# TopLevelMCU.net
KiCad netlist of a schematic drawn in Altium Designer
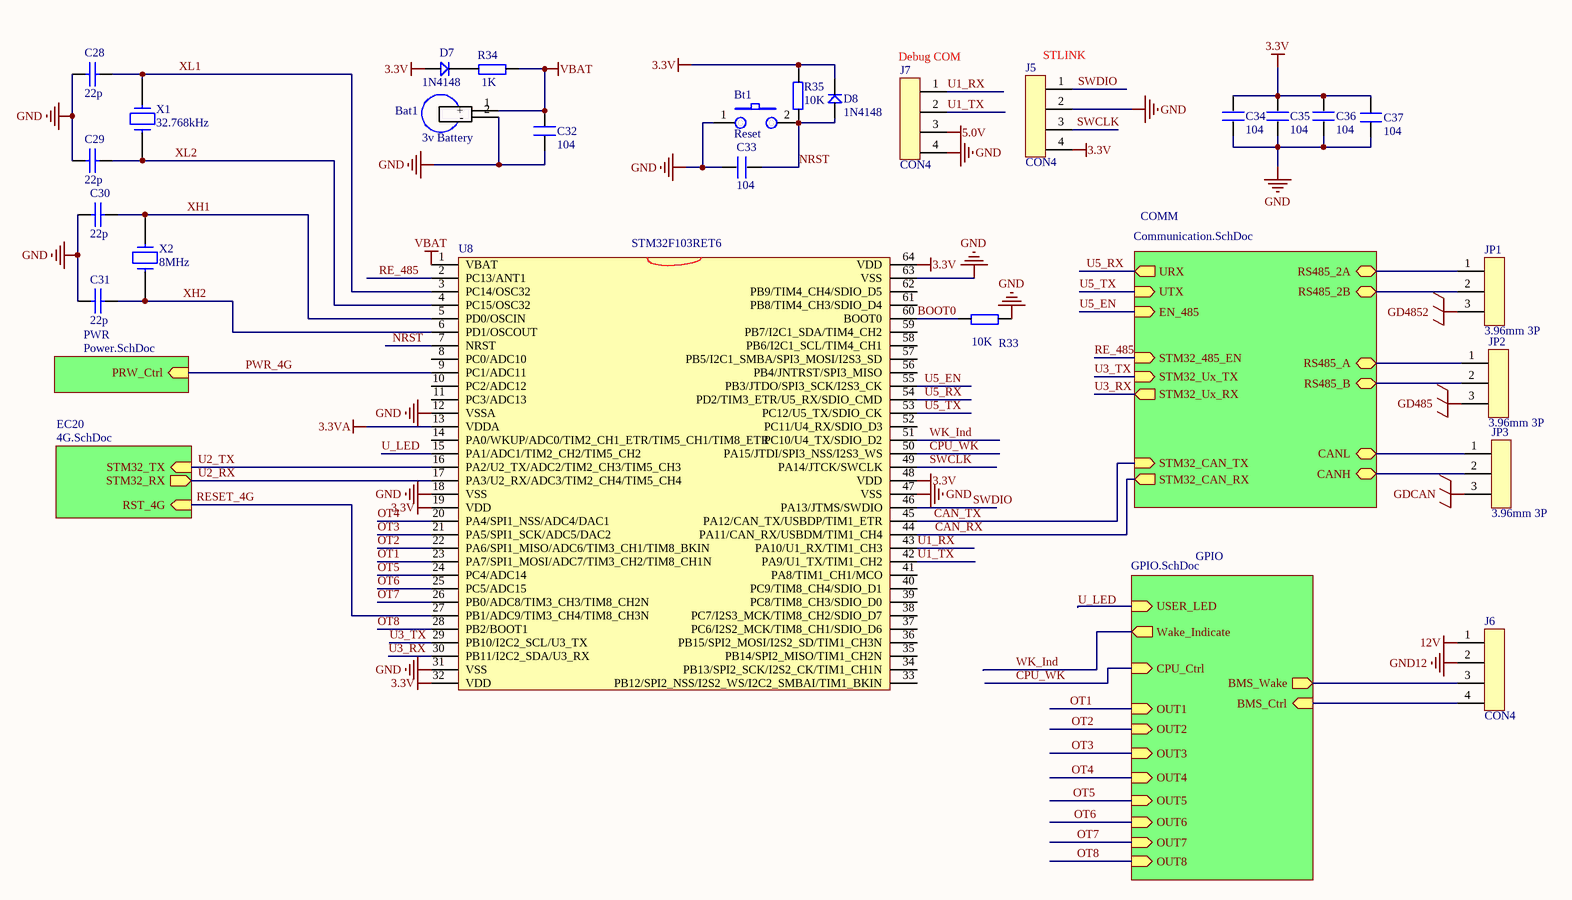
[diagram p0: TopLevelMCU.SchDoc]

(export (version "E")
  (design (tool "Eeschema 10.0.6"))
  (components
    (comp (ref "Bat1") (value "3v Battery") (footprint "BATM") (libsource (lib "stm32") (part "MS621FE")))
    (comp (ref "Bt1")
      (value "Reset")
      (footprint "mypcb:3*6*2.5贴片 微动开关")
      (libsource (lib "stm32") (part "PUSH BUTTON"))
    )
    (comp (ref "C28")
      (value "22p")
      (footprint "0603_C")
      (description "Capacitor")
      (libsource (lib "PLC1") (part "CAP"))
    )
    (comp (ref "C29")
      (value "22p")
      (footprint "0603_C")
      (description "Capacitor")
      (libsource (lib "PLC1") (part "CAP"))
    )
    (comp (ref "C30")
      (value "22p")
      (footprint "0603_C")
      (description "Capacitor")
      (libsource (lib "PLC1") (part "CAP"))
    )
    (comp (ref "C31")
      (value "22p")
      (footprint "0603_C")
      (description "Capacitor")
      (libsource (lib "PLC1") (part "CAP"))
    )
    (comp (ref "C32") (value "104") (footprint "0603_C") (libsource (lib "CORE") (part "C")))
    (comp (ref "C33") (value "104") (footprint "0603_C") (libsource (lib "CORE") (part "C")))
    (comp (ref "C34") (value "104") (footprint "0603_C") (libsource (lib "CORE") (part "C")))
    (comp (ref "C35") (value "104") (footprint "0603_C") (libsource (lib "CORE") (part "C")))
    (comp (ref "C36") (value "104") (footprint "0603_C") (libsource (lib "CORE") (part "C")))
    (comp (ref "C37") (value "104") (footprint "0603_C") (libsource (lib "CORE") (part "C")))
    (comp (ref "D7") (value "1N4148") (footprint "SOD-323") (libsource (lib "CORE") (part "D")))
    (comp (ref "D8") (value "1N4148") (footprint "SOD-323") (libsource (lib "CORE") (part "D")))
    (comp (ref "J5") (value "CON4") (footprint "CON4(2.54)") (libsource (lib "mysch") (part "CON4")))
    (comp (ref "J6") (value "CON4") (footprint "CON4(2.54)") (libsource (lib "BatteryIot-V3") (part "CON4")))
    (comp (ref "J7") (value "CON4") (footprint "CON4(2.54)") (libsource (lib "mysch") (part "CON4")))
    (comp (ref "JP1") (value "3.96mm 3P") (libsource (lib "BatteryIot-V3") (part "CON3")))
    (comp (ref "JP2") (value "3.96mm 3P") (libsource (lib "BatteryIot-V3") (part "CON3")))
    (comp (ref "JP3") (value "3.96mm 3P") (libsource (lib "BatteryIot-V3") (part "CON3")))
    (comp (ref "R33") (value "10K") (footprint "0603_R") (libsource (lib "CORE") (part "R")))
    (comp (ref "R34") (value "1K") (footprint "0603_R") (libsource (lib "CORE") (part "R")))
    (comp (ref "R35") (value "10K") (footprint "0603_R") (libsource (lib "CORE") (part "R")))
    (comp (ref "U8")
      (value "STM32F103RET6")
      (footprint "LQFP64")
      (libsource (lib "CORE") (part "STM32F103RDT6"))
    )
    (comp (ref "X1") (value "32.768kHz") (footprint "XTAL32") (libsource (lib "stm32") (part "Crystal2")))
    (comp (ref "X2") (value "8MHz") (footprint "Crystal_SMD") (libsource (lib "stm32") (part "Crystal2")))
  )
  (nets
    (net (code "1") (name "/BMS_Ctrl") (class "Default")
      (node (ref "J6") (pin "4") (pinfunction "4_4") (pintype "passive"))
    )
    (net (code "2") (name "/BMS_Wake") (class "Default")
      (node (ref "J6") (pin "3") (pinfunction "3_3") (pintype "passive"))
    )
    (net (code "3") (name "/BOOT0") (class "Default")
      (node (ref "R33") (pin "1") (pintype "passive"))
      (node (ref "U8") (pin "60") (pinfunction "BOOT0_60") (pintype "passive"))
    )
    (net (code "4") (name "/CANH") (class "Default")
      (node (ref "JP3") (pin "2") (pinfunction "2_2") (pintype "passive"))
    )
    (net (code "5") (name "/CANL") (class "Default")
      (node (ref "JP3") (pin "1") (pinfunction "1_1") (pintype "passive"))
    )
    (net (code "6") (name "/CAN_RX") (class "Default")
      (node (ref "U8") (pin "44") (pinfunction "PA11/CAN_RX/USBDM/TIM1_CH4_44") (pintype "passive"))
    )
    (net (code "7") (name "/CAN_TX") (class "Default")
      (node (ref "U8") (pin "45") (pinfunction "PA12/CAN_TX/USBDP/TIM1_ETR_45") (pintype "passive"))
    )
    (net (code "8") (name "/CPU_WK") (class "Default")
      (node (ref "U8") (pin "50") (pinfunction "PA15/JTDI/SPI3_NSS/I2S3_WS_50") (pintype "passive"))
    )
    (net (code "9") (name "/NRST") (class "Default")
      (node (ref "Bt1") (pin "2") (pinfunction "2_2") (pintype "passive"))
      (node (ref "C33") (pin "1") (pintype "passive"))
      (node (ref "D8") (pin "1") (pintype "passive"))
      (node (ref "R35") (pin "2") (pintype "passive"))
      (node (ref "U8") (pin "7") (pinfunction "NRST_7") (pintype "passive"))
    )
    (net (code "10") (name "/OT1") (class "Default")
      (node (ref "U8") (pin "23") (pinfunction "PA7/SPI1_MOSI/ADC7/TIM3_CH2/TIM8_CH1N_23") (pintype "passive"))
    )
    (net (code "11") (name "/OT2") (class "Default")
      (node (ref "U8") (pin "22") (pinfunction "PA6/SPI1_MISO/ADC6/TIM3_CH1/TIM8_BKIN_22") (pintype "passive"))
    )
    (net (code "12") (name "/OT3") (class "Default")
      (node (ref "U8") (pin "21") (pinfunction "PA5/SPI1_SCK/ADC5/DAC2_21") (pintype "passive"))
    )
    (net (code "13") (name "/OT4") (class "Default")
      (node (ref "U8") (pin "20") (pinfunction "PA4/SPI1_NSS/ADC4/DAC1_20") (pintype "passive"))
    )
    (net (code "14") (name "/OT5") (class "Default")
      (node (ref "U8") (pin "24") (pinfunction "PC4/ADC14_24") (pintype "passive"))
    )
    (net (code "15") (name "/OT6") (class "Default")
      (node (ref "U8") (pin "25") (pinfunction "PC5/ADC15_25") (pintype "passive"))
    )
    (net (code "16") (name "/OT7") (class "Default")
      (node (ref "U8") (pin "26") (pinfunction "PB0/ADC8/TIM3_CH3/TIM8_CH2N_26") (pintype "passive"))
    )
    (net (code "17") (name "/OT8") (class "Default")
      (node (ref "U8") (pin "28") (pinfunction "PB2/BOOT1_28") (pintype "passive"))
    )
    (net (code "18") (name "/PWR_4G") (class "Default")
      (node (ref "U8") (pin "9") (pinfunction "PC1/ADC11_9") (pintype "passive"))
    )
    (net (code "19") (name "/RESET_4G") (class "Default")
      (node (ref "U8") (pin "27") (pinfunction "PB1/ADC9/TIM3_CH4/TIM8_CH3N_27") (pintype "passive"))
    )
    (net (code "20") (name "/RE_485") (class "Default")
      (node (ref "U8") (pin "2") (pinfunction "PC13/ANT1_2") (pintype "passive"))
    )
    (net (code "21") (name "/RS485_2A") (class "Default")
      (node (ref "JP1") (pin "1") (pinfunction "1_1") (pintype "passive"))
    )
    (net (code "22") (name "/RS485_2B") (class "Default")
      (node (ref "JP1") (pin "2") (pinfunction "2_2") (pintype "passive"))
    )
    (net (code "23") (name "/RS485_A") (class "Default")
      (node (ref "JP2") (pin "1") (pinfunction "1_1") (pintype "passive"))
    )
    (net (code "24") (name "/RS485_B") (class "Default")
      (node (ref "JP2") (pin "2") (pinfunction "2_2") (pintype "passive"))
    )
    (net (code "25") (name "/SWCLK") (class "Default")
      (node (ref "J5") (pin "3") (pinfunction "3_3") (pintype "passive"))
      (node (ref "U8") (pin "49") (pinfunction "PA14/JTCK/SWCLK_49") (pintype "passive"))
    )
    (net (code "26") (name "/SWDIO") (class "Default")
      (node (ref "J5") (pin "1") (pinfunction "1_1") (pintype "passive"))
      (node (ref "U8") (pin "46") (pinfunction "PA13/JTMS/SWDIO_46") (pintype "passive"))
    )
    (net (code "27") (name "/U1_RX") (class "Default")
      (node (ref "J7") (pin "1") (pinfunction "1_1") (pintype "passive"))
      (node (ref "U8") (pin "43") (pinfunction "PA10/U1_RX/TIM1_CH3_43") (pintype "passive"))
    )
    (net (code "28") (name "/U1_TX") (class "Default")
      (node (ref "J7") (pin "2") (pinfunction "2_2") (pintype "passive"))
      (node (ref "U8") (pin "42") (pinfunction "PA9/U1_TX/TIM1_CH2_42") (pintype "passive"))
    )
    (net (code "29") (name "/U2_RX") (class "Default")
      (node (ref "U8") (pin "17") (pinfunction "PA3/U2_RX/ADC3/TIM2_CH4/TIM5_CH4_17") (pintype "passive"))
    )
    (net (code "30") (name "/U2_TX") (class "Default")
      (node (ref "U8") (pin "16") (pinfunction "PA2/U2_TX/ADC2/TIM2_CH3/TIM5_CH3_16") (pintype "passive"))
    )
    (net (code "31") (name "/U3_RX") (class "Default")
      (node (ref "U8") (pin "30") (pinfunction "PB11/I2C2_SDA/U3_RX_30") (pintype "passive"))
    )
    (net (code "32") (name "/U3_TX") (class "Default")
      (node (ref "U8") (pin "29") (pinfunction "PB10/I2C2_SCL/U3_TX_29") (pintype "passive"))
    )
    (net (code "33") (name "/U5_EN") (class "Default")
      (node (ref "U8") (pin "55") (pinfunction "PB3/JTDO/SPI3_SCK/I2S3_CK_55") (pintype "passive"))
    )
    (net (code "34") (name "/U5_RX") (class "Default")
      (node (ref "U8") (pin "54") (pinfunction "PD2/TIM3_ETR/U5_RX/SDIO_CMD_54") (pintype "passive"))
    )
    (net (code "35") (name "/U5_TX") (class "Default")
      (node (ref "U8") (pin "53") (pinfunction "PC12/U5_TX/SDIO_CK_53") (pintype "passive"))
    )
    (net (code "36") (name "/U_LED") (class "Default")
      (node (ref "U8") (pin "15") (pinfunction "PA1/ADC1/TIM2_CH2/TIM5_CH2_15") (pintype "passive"))
    )
    (net (code "37") (name "/WK_Ind") (class "Default")
      (node (ref "U8") (pin "51") (pinfunction "PC10/U4_TX/SDIO_D2_51") (pintype "passive"))
    )
    (net (code "38") (name "/XH1") (class "Default")
      (node (ref "C30") (pin "1") (pinfunction "1_1") (pintype "passive"))
      (node (ref "U8") (pin "5") (pinfunction "PD0/OSCIN_5") (pintype "passive"))
      (node (ref "X2") (pin "1") (pinfunction "1_1") (pintype "passive"))
    )
    (net (code "39") (name "/XH2") (class "Default")
      (node (ref "C31") (pin "1") (pinfunction "1_1") (pintype "passive"))
      (node (ref "U8") (pin "6") (pinfunction "PD1/OSCOUT_6") (pintype "passive"))
      (node (ref "X2") (pin "2") (pinfunction "2_2") (pintype "passive"))
    )
    (net (code "40") (name "/XL1") (class "Default")
      (node (ref "C28") (pin "1") (pinfunction "1_1") (pintype "passive"))
      (node (ref "U8") (pin "3") (pinfunction "PC14/OSC32_3") (pintype "passive"))
      (node (ref "X1") (pin "1") (pinfunction "1_1") (pintype "passive"))
    )
    (net (code "41") (name "/XL2") (class "Default")
      (node (ref "C29") (pin "1") (pinfunction "1_1") (pintype "passive"))
      (node (ref "U8") (pin "4") (pinfunction "PC15/OSC32_4") (pintype "passive"))
      (node (ref "X1") (pin "2") (pinfunction "2_2") (pintype "passive"))
    )
    (net (code "42") (name "3.3V") (class "Default")
      (node (ref "C34") (pin "1") (pintype "passive"))
      (node (ref "C35") (pin "1") (pintype "passive"))
      (node (ref "C36") (pin "1") (pintype "passive"))
      (node (ref "C37") (pin "1") (pintype "passive"))
      (node (ref "D7") (pin "1") (pintype "passive"))
      (node (ref "D8") (pin "2") (pintype "passive"))
      (node (ref "J5") (pin "4") (pinfunction "4_4") (pintype "passive"))
      (node (ref "R35") (pin "1") (pintype "passive"))
      (node (ref "U8") (pin "19") (pinfunction "VDD_19") (pintype "passive"))
      (node (ref "U8") (pin "32") (pinfunction "VDD_32") (pintype "passive"))
      (node (ref "U8") (pin "48") (pinfunction "VDD_48") (pintype "passive"))
      (node (ref "U8") (pin "64") (pinfunction "VDD_64") (pintype "passive"))
    )
    (net (code "43") (name "3.3VA") (class "Default")
      (node (ref "U8") (pin "13") (pinfunction "VDDA_13") (pintype "passive"))
    )
    (net (code "44") (name "5.0V") (class "Default")
      (node (ref "J7") (pin "3") (pinfunction "3_3") (pintype "passive"))
    )
    (net (code "45") (name "12V") (class "Default")
      (node (ref "J6") (pin "1") (pinfunction "1_1") (pintype "passive"))
    )
    (net (code "46") (name "GD485") (class "Default")
      (node (ref "JP2") (pin "3") (pinfunction "3_3") (pintype "passive"))
    )
    (net (code "47") (name "GD4852") (class "Default")
      (node (ref "JP1") (pin "3") (pinfunction "3_3") (pintype "passive"))
    )
    (net (code "48") (name "GDCAN") (class "Default")
      (node (ref "JP3") (pin "3") (pinfunction "3_3") (pintype "passive"))
    )
    (net (code "49") (name "GND") (class "Default")
      (node (ref "Bat1") (pin "2") (pinfunction "-_2") (pintype "passive"))
      (node (ref "Bt1") (pin "1") (pinfunction "1_1") (pintype "passive"))
      (node (ref "C28") (pin "2") (pinfunction "2_2") (pintype "passive"))
      (node (ref "C29") (pin "2") (pinfunction "2_2") (pintype "passive"))
      (node (ref "C30") (pin "2") (pinfunction "2_2") (pintype "passive"))
      (node (ref "C31") (pin "2") (pinfunction "2_2") (pintype "passive"))
      (node (ref "C32") (pin "2") (pintype "passive"))
      (node (ref "C33") (pin "2") (pintype "passive"))
      (node (ref "C34") (pin "2") (pintype "passive"))
      (node (ref "C35") (pin "2") (pintype "passive"))
      (node (ref "C36") (pin "2") (pintype "passive"))
      (node (ref "C37") (pin "2") (pintype "passive"))
      (node (ref "J5") (pin "2") (pinfunction "2_2") (pintype "passive"))
      (node (ref "J7") (pin "4") (pinfunction "4_4") (pintype "passive"))
      (node (ref "R33") (pin "2") (pintype "passive"))
      (node (ref "U8") (pin "12") (pinfunction "VSSA_12") (pintype "passive"))
      (node (ref "U8") (pin "18") (pinfunction "VSS_18") (pintype "passive"))
      (node (ref "U8") (pin "31") (pinfunction "VSS_31") (pintype "passive"))
      (node (ref "U8") (pin "47") (pinfunction "VSS_47") (pintype "passive"))
      (node (ref "U8") (pin "63") (pinfunction "VSS_63") (pintype "passive"))
    )
    (net (code "50") (name "GND12") (class "Default")
      (node (ref "J6") (pin "2") (pinfunction "2_2") (pintype "passive"))
    )
    (net (code "51") (name "Net-(D7-Pad2)") (class "Default")
      (node (ref "D7") (pin "2") (pintype "passive"))
      (node (ref "R34") (pin "1") (pintype "passive"))
    )
    (net (code "52") (name "VBAT") (class "Default")
      (node (ref "Bat1") (pin "1") (pinfunction "+_1") (pintype "passive"))
      (node (ref "C32") (pin "1") (pintype "passive"))
      (node (ref "R34") (pin "2") (pintype "passive"))
      (node (ref "U8") (pin "1") (pinfunction "VBAT_1") (pintype "passive"))
    )
    (net (code "53") (name "unconnected-(U8-PA0{slash}WKUP{slash}ADC0{slash}TIM2_CH1_ETR{slash}TIM5_CH1{slash}TIM8_ETR-Pad14)") (class "Default")
      (node (ref "U8") (pin "14") (pinfunction "PA0/WKUP/ADC0/TIM2_CH1_ETR/TIM5_CH1/TIM8_ETR_14") (pintype "passive"))
    )
    (net (code "54") (name "unconnected-(U8-PA8{slash}TIM1_CH1{slash}MCO-Pad41)") (class "Default")
      (node (ref "U8") (pin "41") (pinfunction "PA8/TIM1_CH1/MCO_41") (pintype "passive"))
    )
    (net (code "55") (name "unconnected-(U8-PB4{slash}JNTRST{slash}SPI3_MISO-Pad56)") (class "Default")
      (node (ref "U8") (pin "56") (pinfunction "PB4/JNTRST/SPI3_MISO_56") (pintype "passive"))
    )
    (net (code "56") (name "unconnected-(U8-PB5{slash}I2C1_SMBA{slash}SPI3_MOSI{slash}I2S3_SD-Pad57)") (class "Default")
      (node (ref "U8") (pin "57") (pinfunction "PB5/I2C1_SMBA/SPI3_MOSI/I2S3_SD_57") (pintype "passive"))
    )
    (net (code "57") (name "unconnected-(U8-PB6{slash}I2C1_SCL{slash}TIM4_CH1-Pad58)") (class "Default")
      (node (ref "U8") (pin "58") (pinfunction "PB6/I2C1_SCL/TIM4_CH1_58") (pintype "passive"))
    )
    (net (code "58") (name "unconnected-(U8-PB7{slash}I2C1_SDA{slash}TIM4_CH2-Pad59)") (class "Default")
      (node (ref "U8") (pin "59") (pinfunction "PB7/I2C1_SDA/TIM4_CH2_59") (pintype "passive"))
    )
    (net (code "59") (name "unconnected-(U8-PB8{slash}TIM4_CH3{slash}SDIO_D4-Pad61)") (class "Default")
      (node (ref "U8") (pin "61") (pinfunction "PB8/TIM4_CH3/SDIO_D4_61") (pintype "passive"))
    )
    (net (code "60") (name "unconnected-(U8-PB9{slash}TIM4_CH4{slash}SDIO_D5-Pad62)") (class "Default")
      (node (ref "U8") (pin "62") (pinfunction "PB9/TIM4_CH4/SDIO_D5_62") (pintype "passive"))
    )
    (net (code "61") (name "unconnected-(U8-PB12{slash}SPI2_NSS{slash}I2S2_WS{slash}I2C2_SMBAI{slash}TIM1_BKIN-Pad33)") (class "Default")
      (node (ref "U8") (pin "33") (pinfunction "PB12/SPI2_NSS/I2S2_WS/I2C2_SMBAI/TIM1_BKIN_33") (pintype "passive"))
    )
    (net (code "62") (name "unconnected-(U8-PB13{slash}SPI2_SCK{slash}I2S2_CK{slash}TIM1_CH1N-Pad34)") (class "Default")
      (node (ref "U8") (pin "34") (pinfunction "PB13/SPI2_SCK/I2S2_CK/TIM1_CH1N_34") (pintype "passive"))
    )
    (net (code "63") (name "unconnected-(U8-PB14{slash}SPI2_MISO{slash}TIM1_CH2N-Pad35)") (class "Default")
      (node (ref "U8") (pin "35") (pinfunction "PB14/SPI2_MISO/TIM1_CH2N_35") (pintype "passive"))
    )
    (net (code "64") (name "unconnected-(U8-PB15{slash}SPI2_MOSI{slash}I2S2_SD{slash}TIM1_CH3N-Pad36)") (class "Default")
      (node (ref "U8") (pin "36") (pinfunction "PB15/SPI2_MOSI/I2S2_SD/TIM1_CH3N_36") (pintype "passive"))
    )
    (net (code "65") (name "unconnected-(U8-PC0{slash}ADC10-Pad8)") (class "Default")
      (node (ref "U8") (pin "8") (pinfunction "PC0/ADC10_8") (pintype "passive"))
    )
    (net (code "66") (name "unconnected-(U8-PC2{slash}ADC12-Pad10)") (class "Default")
      (node (ref "U8") (pin "10") (pinfunction "PC2/ADC12_10") (pintype "passive"))
    )
    (net (code "67") (name "unconnected-(U8-PC3{slash}ADC13-Pad11)") (class "Default")
      (node (ref "U8") (pin "11") (pinfunction "PC3/ADC13_11") (pintype "passive"))
    )
    (net (code "68") (name "unconnected-(U8-PC6{slash}I2S2_MCK{slash}TIM8_CH1{slash}SDIO_D6-Pad37)") (class "Default")
      (node (ref "U8") (pin "37") (pinfunction "PC6/I2S2_MCK/TIM8_CH1/SDIO_D6_37") (pintype "passive"))
    )
    (net (code "69") (name "unconnected-(U8-PC7{slash}I2S3_MCK{slash}TIM8_CH2{slash}SDIO_D7-Pad38)") (class "Default")
      (node (ref "U8") (pin "38") (pinfunction "PC7/I2S3_MCK/TIM8_CH2/SDIO_D7_38") (pintype "passive"))
    )
    (net (code "70") (name "unconnected-(U8-PC8{slash}TIM8_CH3{slash}SDIO_D0-Pad39)") (class "Default")
      (node (ref "U8") (pin "39") (pinfunction "PC8/TIM8_CH3/SDIO_D0_39") (pintype "passive"))
    )
    (net (code "71") (name "unconnected-(U8-PC9{slash}TIM8_CH4{slash}SDIO_D1-Pad40)") (class "Default")
      (node (ref "U8") (pin "40") (pinfunction "PC9/TIM8_CH4/SDIO_D1_40") (pintype "passive"))
    )
    (net (code "72") (name "unconnected-(U8-PC11{slash}U4_RX{slash}SDIO_D3-Pad52)") (class "Default")
      (node (ref "U8") (pin "52") (pinfunction "PC11/U4_RX/SDIO_D3_52") (pintype "passive"))
    )
  )
)
